# 36Pin_SuperSeal_Conn.net
KiCad netlist of a schematic drawn in Altium Designer
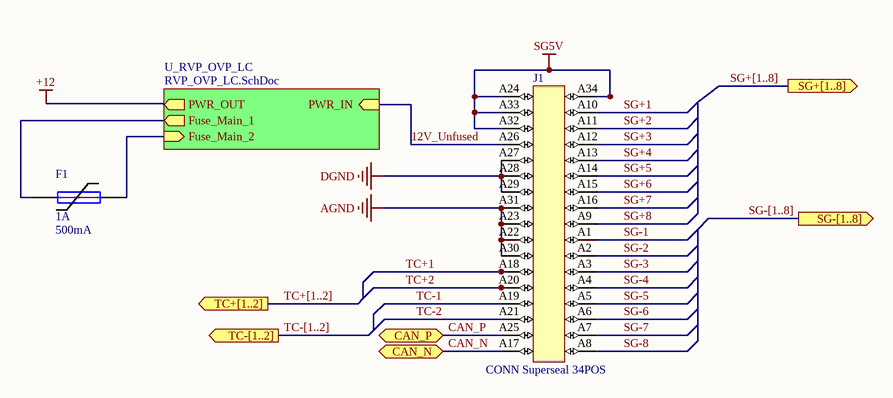
[diagram p0: 36Pin_SuperSeal_Conn.SchDoc]

(export (version "E")
  (design (tool "Eeschema 10.0.6"))
  (components
    (comp (ref "F1")
      (value "1A")
      (footprint "PTC Fuse 1206/3216")
      (description "Fuse")
      (fields
        (field (name "I_HOLD") "500mA")
        (field (name "MFRPARTNO") "1206L050/15YR")
        (field (name "PUBLISHER") "Altium Limited")
        (field (name "CREATED_BY") "Angel")
      )
      (libsource (lib "Altium-Lib") (part "PTC Fuse"))
    )
    (comp (ref "J1")
      (value "CONN Superseal 34POS")
      (footprint "Superseal 34POS")
      (description "Connector Header Through Hole, Right Angle 34 position 0.118\" (3.00mm)")
      (fields (field (name "MFRPARTNO") "6437288-1"))
      (libsource (lib "Altium-Lib") (part "CONN Superseal 34POS"))
    )
  )
  (nets
    (net (code "2") (name "/12V_Unfused") (class "Default")
      (node (ref "J1") (pin "A26") (pintype "bidirectional"))
    )
    (net (code "3") (name "/CAN_N") (class "Default") (node (ref "J1") (pin "A17") (pintype "bidirectional")))
    (net (code "4") (name "/CAN_P") (class "Default") (node (ref "J1") (pin "A25") (pintype "bidirectional")))
    (net (code "5") (name "/Fuse_Main_1") (class "Default")
      (node (ref "F1") (pin "1") (pinfunction "1_1") (pintype "passive"))
    )
    (net (code "6") (name "/Fuse_Main_2") (class "Default")
      (node (ref "F1") (pin "2") (pinfunction "2_2") (pintype "passive"))
    )
    (net (code "7") (name "/SG+1") (class "Default") (node (ref "J1") (pin "A10") (pintype "bidirectional")))
    (net (code "8") (name "/SG+2") (class "Default") (node (ref "J1") (pin "A11") (pintype "bidirectional")))
    (net (code "9") (name "/SG+3") (class "Default") (node (ref "J1") (pin "A12") (pintype "bidirectional")))
    (net (code "10") (name "/SG+4") (class "Default") (node (ref "J1") (pin "A13") (pintype "bidirectional")))
    (net (code "11") (name "/SG+5") (class "Default") (node (ref "J1") (pin "A14") (pintype "bidirectional")))
    (net (code "12") (name "/SG+6") (class "Default") (node (ref "J1") (pin "A15") (pintype "bidirectional")))
    (net (code "13") (name "/SG+7") (class "Default") (node (ref "J1") (pin "A16") (pintype "bidirectional")))
    (net (code "14") (name "/SG+8") (class "Default") (node (ref "J1") (pin "A9") (pintype "bidirectional")))
    (net (code "16") (name "/SG-1") (class "Default") (node (ref "J1") (pin "A1") (pintype "bidirectional")))
    (net (code "17") (name "/SG-2") (class "Default") (node (ref "J1") (pin "A2") (pintype "bidirectional")))
    (net (code "18") (name "/SG-3") (class "Default") (node (ref "J1") (pin "A3") (pintype "bidirectional")))
    (net (code "19") (name "/SG-4") (class "Default") (node (ref "J1") (pin "A4") (pintype "bidirectional")))
    (net (code "20") (name "/SG-5") (class "Default") (node (ref "J1") (pin "A5") (pintype "bidirectional")))
    (net (code "21") (name "/SG-6") (class "Default") (node (ref "J1") (pin "A6") (pintype "bidirectional")))
    (net (code "22") (name "/SG-7") (class "Default") (node (ref "J1") (pin "A7") (pintype "bidirectional")))
    (net (code "23") (name "/SG-8") (class "Default") (node (ref "J1") (pin "A8") (pintype "bidirectional")))
    (net (code "25") (name "/TC+1") (class "Default") (node (ref "J1") (pin "A18") (pintype "bidirectional")))
    (net (code "26") (name "/TC+2") (class "Default") (node (ref "J1") (pin "A20") (pintype "bidirectional")))
    (net (code "28") (name "/TC-1") (class "Default") (node (ref "J1") (pin "A19") (pintype "bidirectional")))
    (net (code "29") (name "/TC-2") (class "Default") (node (ref "J1") (pin "A21") (pintype "bidirectional")))
    (net (code "31") (name "AGND") (class "Default")
      (node (ref "J1") (pin "A22") (pintype "bidirectional"))
      (node (ref "J1") (pin "A23") (pintype "bidirectional"))
      (node (ref "J1") (pin "A30") (pintype "bidirectional"))
      (node (ref "J1") (pin "A31") (pintype "bidirectional"))
    )
    (net (code "32") (name "DGND") (class "Default")
      (node (ref "J1") (pin "A27") (pintype "bidirectional"))
      (node (ref "J1") (pin "A28") (pintype "bidirectional"))
      (node (ref "J1") (pin "A29") (pintype "bidirectional"))
    )
    (net (code "33") (name "SG5V") (class "Default")
      (node (ref "J1") (pin "A24") (pintype "bidirectional"))
      (node (ref "J1") (pin "A32") (pintype "bidirectional"))
      (node (ref "J1") (pin "A33") (pintype "bidirectional"))
      (node (ref "J1") (pin "A34") (pintype "bidirectional"))
    )
  )
)
